# Slave.net
KiCad netlist of a schematic drawn in Altium Designer
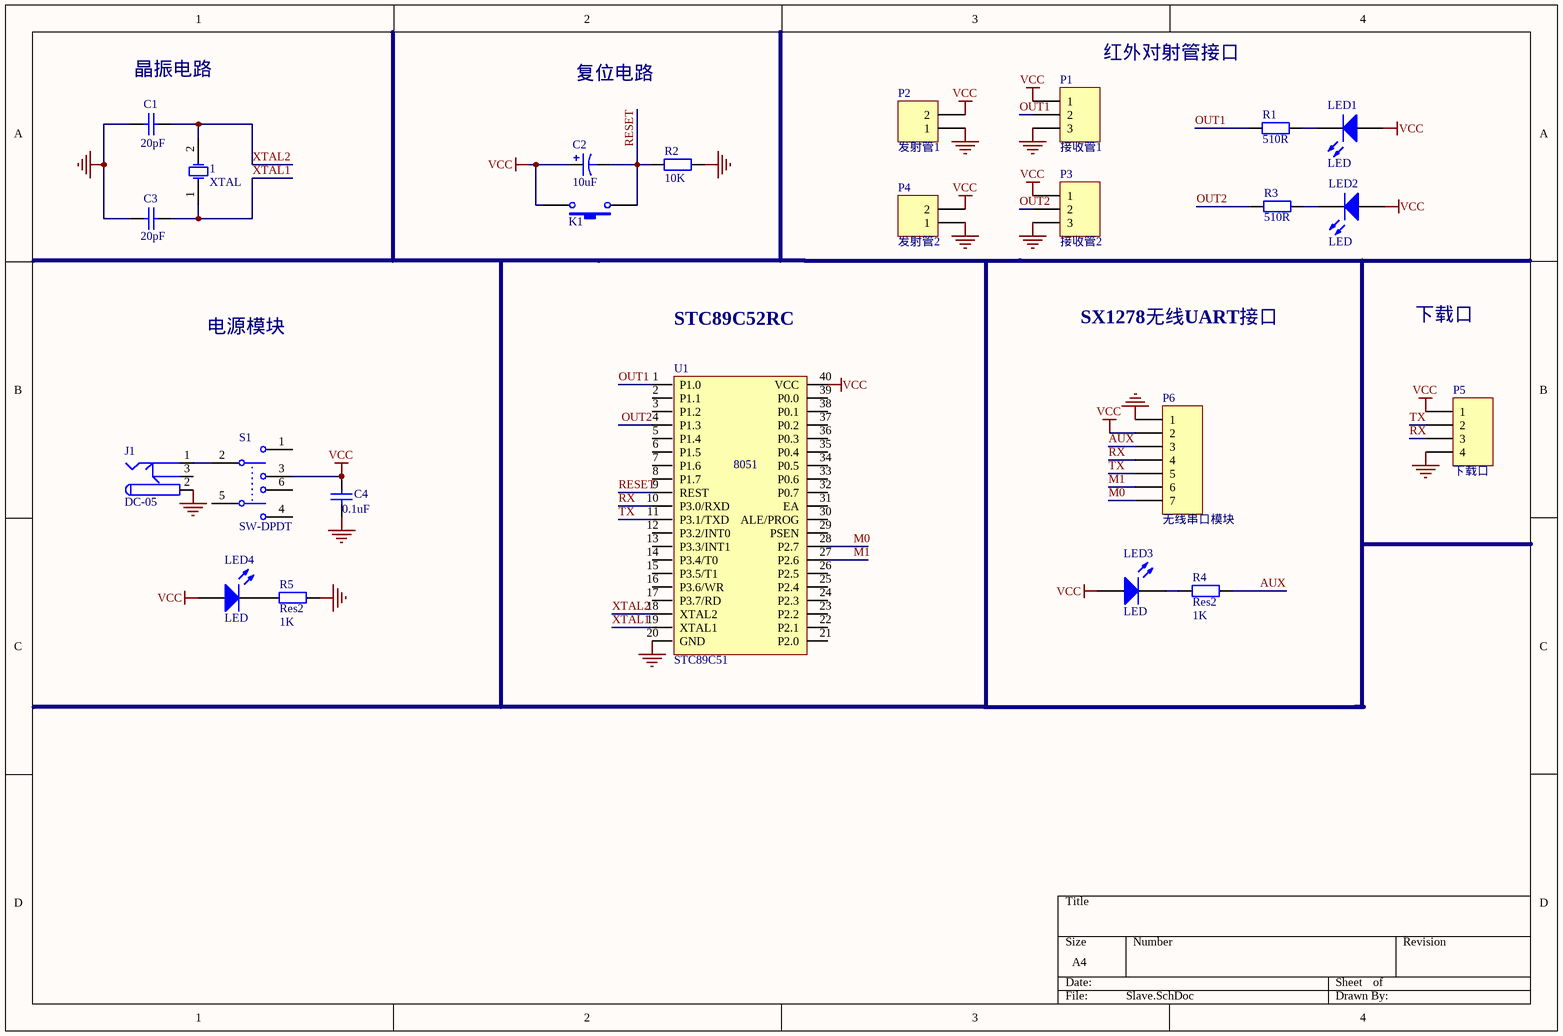
[diagram p0: Slave.SchDoc]

(export (version "E")
  (design (tool "Eeschema 10.0.6"))
  (components
    (comp (ref "1")
      (value "XTAL")
      (footprint "XTAL_US")
      (description "Crystal Oscillator")
      (fields (field (name "PUBLISHER") "Altium Limited"))
      (libsource (lib "Miscellaneous Devices") (part "XTAL"))
    )
    (comp (ref "C1")
      (value "20pF")
      (footprint "RAD-0.1")
      (description "Capacitor")
      (fields (field (name "Comment") "Cap") (field (name "PUBLISHER") "Altium Limited"))
      (libsource (lib "Miscellaneous Devices") (part "Cap"))
    )
    (comp (ref "C2")
      (value "10uF")
      (footprint "RB.1/.2")
      (description "Polarized Capacitor (Radial)")
      (fields (field (name "Comment") "Cap Pol1") (field (name "PUBLISHER") "Altium Limited"))
      (libsource (lib "Miscellaneous Devices") (part "Cap Pol1"))
    )
    (comp (ref "C3")
      (value "20pF")
      (footprint "RAD-0.1")
      (description "Capacitor")
      (fields (field (name "Comment") "Cap") (field (name "PUBLISHER") "Altium Limited"))
      (libsource (lib "Miscellaneous Devices") (part "Cap"))
    )
    (comp (ref "C4")
      (value "0.1uF")
      (footprint "RAD-0.1")
      (description "Capacitor")
      (fields (field (name "Comment") "Cap") (field (name "PUBLISHER") "Altium Limited"))
      (libsource (lib "Miscellaneous Devices") (part "Cap"))
    )
    (comp (ref "J1") (value "DC-05") (footprint "DC-05") (libsource (lib "My library") (part "DC-05")))
    (comp (ref "K1") (value "四脚按键") (footprint "四脚按键") (libsource (lib "My library") (part "四脚按键")))
    (comp (ref "LED1") (value "LED") (footprint "LED") (libsource (lib "My library") (part "LED")))
    (comp (ref "LED2") (value "LED") (footprint "LED") (libsource (lib "My library") (part "LED")))
    (comp (ref "LED3") (value "LED") (footprint "LED") (libsource (lib "My library") (part "LED")))
    (comp (ref "LED4") (value "LED") (footprint "LED") (libsource (lib "My library") (part "LED")))
    (comp (ref "P1")
      (value "接收管1")
      (footprint "HDR1X3")
      (description "Header, 3-Pin")
      (fields (field (name "PUBLISHER") "Altium Limited"))
      (libsource (lib "Miscellaneous Connectors") (part "Header 3"))
    )
    (comp (ref "P2")
      (value "发射管1")
      (footprint "HDR1X2")
      (description "Header, 2-Pin")
      (fields (field (name "PUBLISHER") "Altium Limited"))
      (libsource (lib "Miscellaneous Connectors") (part "Header 2"))
    )
    (comp (ref "P3")
      (value "接收管2")
      (footprint "HDR1X3")
      (description "Header, 3-Pin")
      (fields (field (name "PUBLISHER") "Altium Limited"))
      (libsource (lib "Miscellaneous Connectors") (part "Header 3"))
    )
    (comp (ref "P4")
      (value "发射管2")
      (footprint "HDR1X2")
      (description "Header, 2-Pin")
      (fields (field (name "PUBLISHER") "Altium Limited"))
      (libsource (lib "Miscellaneous Connectors") (part "Header 2"))
    )
    (comp (ref "P5")
      (value "下载口")
      (footprint "HDR1X4")
      (description "Header, 4-Pin")
      (fields (field (name "PUBLISHER") "Altium Limited"))
      (libsource (lib "Miscellaneous Connectors") (part "Header 4"))
    )
    (comp (ref "P6")
      (value "无线串口模块")
      (footprint "AS32-TTL-100")
      (description "Header, 7-Pin")
      (fields (field (name "PUBLISHER") "Altium Limited"))
      (libsource (lib "Miscellaneous Connectors") (part "Header 7"))
    )
    (comp (ref "R1")
      (value "510R")
      (footprint "AXIAL-0.4")
      (description "Resistor")
      (fields (field (name "Comment") "Res2") (field (name "PUBLISHER") "Altium Limited"))
      (libsource (lib "Miscellaneous Devices") (part "Res2"))
    )
    (comp (ref "R2")
      (value "10K")
      (footprint "AXIAL-0.4")
      (description "Resistor")
      (fields (field (name "Comment") "Res2") (field (name "PUBLISHER") "Altium Limited"))
      (libsource (lib "Miscellaneous Devices") (part "Res2"))
    )
    (comp (ref "R3")
      (value "510R")
      (footprint "AXIAL-0.4")
      (description "Resistor")
      (fields (field (name "Comment") "Res2") (field (name "PUBLISHER") "Altium Limited"))
      (libsource (lib "Miscellaneous Devices") (part "Res2"))
    )
    (comp (ref "R4")
      (value "Res2")
      (footprint "AXIAL-0.4")
      (description "Resistor")
      (fields (field (name "ALTIUM_VALUE") "1K") (field (name "PUBLISHER") "Altium Limited"))
      (libsource (lib "Miscellaneous Devices") (part "Res2"))
    )
    (comp (ref "R5")
      (value "Res2")
      (footprint "AXIAL-0.4")
      (description "Resistor")
      (fields (field (name "ALTIUM_VALUE") "1K") (field (name "PUBLISHER") "Altium Limited"))
      (libsource (lib "Miscellaneous Devices") (part "Res2"))
    )
    (comp (ref "S1")
      (value "SW-DPDT")
      (footprint "SWITCH_B1")
      (description "单刀双掷开关")
      (fields (field (name "PUBLISHER") "Altium Limited"))
      (libsource (lib "Fszhang") (part "SW-DPDT"))
    )
    (comp (ref "U1") (value "STC89C51") (footprint "DIP-40") (libsource (lib "My library") (part "STC89C51")))
  )
  (nets
    (net (code "1") (name "/AUX") (class "Default")
      (node (ref "P6") (pin "3") (pinfunction "3_3") (pintype "passive"))
      (node (ref "R4") (pin "2") (pinfunction "2_2") (pintype "passive"))
    )
    (net (code "2") (name "/M0") (class "Default")
      (node (ref "P6") (pin "7") (pinfunction "7_7") (pintype "passive"))
      (node (ref "U1") (pin "28") (pinfunction "P2.7_28") (pintype "passive"))
    )
    (net (code "3") (name "/M1") (class "Default")
      (node (ref "P6") (pin "6") (pinfunction "6_6") (pintype "passive"))
      (node (ref "U1") (pin "27") (pinfunction "P2.6_27") (pintype "passive"))
    )
    (net (code "4") (name "/OUT1") (class "Default")
      (node (ref "P1") (pin "2") (pinfunction "2_2") (pintype "passive"))
      (node (ref "R1") (pin "1") (pinfunction "1_1") (pintype "passive"))
      (node (ref "U1") (pin "1") (pinfunction "P1.0_1") (pintype "passive"))
    )
    (net (code "5") (name "/OUT2") (class "Default")
      (node (ref "P3") (pin "2") (pinfunction "2_2") (pintype "passive"))
      (node (ref "R3") (pin "1") (pinfunction "1_1") (pintype "passive"))
      (node (ref "U1") (pin "4") (pinfunction "P1.3_4") (pintype "passive"))
    )
    (net (code "6") (name "/RESET") (class "Default")
      (node (ref "C2") (pin "2") (pinfunction "2_2") (pintype "passive"))
      (node (ref "K1") (pin "1") (pinfunction "1_1") (pintype "passive"))
      (node (ref "R2") (pin "1") (pinfunction "1_1") (pintype "passive"))
      (node (ref "U1") (pin "9") (pinfunction "REST_9") (pintype "passive"))
    )
    (net (code "7") (name "/RX") (class "Default")
      (node (ref "P5") (pin "3") (pinfunction "3_3") (pintype "passive"))
      (node (ref "P6") (pin "4") (pinfunction "4_4") (pintype "passive"))
      (node (ref "U1") (pin "10") (pinfunction "P3.0/RXD_10") (pintype "passive"))
    )
    (net (code "8") (name "/TX") (class "Default")
      (node (ref "P5") (pin "2") (pinfunction "2_2") (pintype "passive"))
      (node (ref "P6") (pin "5") (pinfunction "5_5") (pintype "passive"))
      (node (ref "U1") (pin "11") (pinfunction "P3.1/TXD_11") (pintype "passive"))
    )
    (net (code "9") (name "/XTAL1") (class "Default")
      (node (ref "1") (pin "1") (pinfunction "OSC1_1") (pintype "passive"))
      (node (ref "C3") (pin "2") (pinfunction "2_2") (pintype "passive"))
      (node (ref "U1") (pin "19") (pinfunction "XTAL1_19") (pintype "passive"))
    )
    (net (code "10") (name "/XTAL2") (class "Default")
      (node (ref "1") (pin "2") (pinfunction "OSC2_2") (pintype "passive"))
      (node (ref "C1") (pin "2") (pinfunction "2_2") (pintype "passive"))
      (node (ref "U1") (pin "18") (pinfunction "XTAL2_18") (pintype "passive"))
    )
    (net (code "11") (name "GND") (class "Default")
      (node (ref "C1") (pin "1") (pinfunction "1_1") (pintype "passive"))
      (node (ref "C3") (pin "1") (pinfunction "1_1") (pintype "passive"))
      (node (ref "C4") (pin "1") (pinfunction "1_1") (pintype "passive"))
      (node (ref "J1") (pin "2") (pinfunction "2_2") (pintype "passive"))
      (node (ref "P1") (pin "3") (pinfunction "3_3") (pintype "passive"))
      (node (ref "P2") (pin "1") (pinfunction "1_1") (pintype "passive"))
      (node (ref "P3") (pin "3") (pinfunction "3_3") (pintype "passive"))
      (node (ref "P4") (pin "1") (pinfunction "1_1") (pintype "passive"))
      (node (ref "P5") (pin "4") (pinfunction "4_4") (pintype "passive"))
      (node (ref "P6") (pin "1") (pinfunction "1_1") (pintype "passive"))
      (node (ref "R2") (pin "2") (pinfunction "2_2") (pintype "passive"))
      (node (ref "R5") (pin "2") (pinfunction "2_2") (pintype "passive"))
      (node (ref "U1") (pin "20") (pinfunction "GND_20") (pintype "passive"))
    )
    (net (code "12") (name "Net-(J1-Pad1)") (class "Default")
      (node (ref "J1") (pin "1") (pinfunction "1_1") (pintype "passive"))
      (node (ref "S1") (pin "2") (pinfunction "2_2") (pintype "passive"))
    )
    (net (code "13") (name "Net-(LED1-Pad2)") (class "Default")
      (node (ref "LED1") (pin "2") (pinfunction "2_2") (pintype "passive"))
      (node (ref "R1") (pin "2") (pinfunction "2_2") (pintype "passive"))
    )
    (net (code "14") (name "Net-(LED2-Pad2)") (class "Default")
      (node (ref "LED2") (pin "2") (pinfunction "2_2") (pintype "passive"))
      (node (ref "R3") (pin "2") (pinfunction "2_2") (pintype "passive"))
    )
    (net (code "15") (name "Net-(LED3-Pad2)") (class "Default")
      (node (ref "LED3") (pin "2") (pinfunction "2_2") (pintype "passive"))
      (node (ref "R4") (pin "1") (pinfunction "1_1") (pintype "passive"))
    )
    (net (code "16") (name "Net-(LED4-Pad2)") (class "Default")
      (node (ref "LED4") (pin "2") (pinfunction "2_2") (pintype "passive"))
      (node (ref "R5") (pin "1") (pinfunction "1_1") (pintype "passive"))
    )
    (net (code "17") (name "VCC") (class "Default")
      (node (ref "C2") (pin "1") (pinfunction "1_1") (pintype "passive"))
      (node (ref "C4") (pin "2") (pinfunction "2_2") (pintype "passive"))
      (node (ref "K1") (pin "2") (pinfunction "2_2") (pintype "passive"))
      (node (ref "LED1") (pin "1") (pinfunction "1_1") (pintype "passive"))
      (node (ref "LED2") (pin "1") (pinfunction "1_1") (pintype "passive"))
      (node (ref "LED3") (pin "1") (pinfunction "1_1") (pintype "passive"))
      (node (ref "LED4") (pin "1") (pinfunction "1_1") (pintype "passive"))
      (node (ref "P1") (pin "1") (pinfunction "1_1") (pintype "passive"))
      (node (ref "P2") (pin "2") (pinfunction "2_2") (pintype "passive"))
      (node (ref "P3") (pin "1") (pinfunction "1_1") (pintype "passive"))
      (node (ref "P4") (pin "2") (pinfunction "2_2") (pintype "passive"))
      (node (ref "P5") (pin "1") (pinfunction "1_1") (pintype "passive"))
      (node (ref "P6") (pin "2") (pinfunction "2_2") (pintype "passive"))
      (node (ref "S1") (pin "3") (pinfunction "3_3") (pintype "passive"))
      (node (ref "U1") (pin "40") (pinfunction "VCC_40") (pintype "passive"))
    )
    (net (code "18") (name "unconnected-(J1-Pad3)") (class "Default")
      (node (ref "J1") (pin "3") (pinfunction "3_3") (pintype "passive"))
    )
    (net (code "19") (name "unconnected-(S1-Pad1)") (class "Default")
      (node (ref "S1") (pin "1") (pinfunction "1_1") (pintype "passive"))
    )
    (net (code "20") (name "unconnected-(S1-Pad4)") (class "Default")
      (node (ref "S1") (pin "4") (pinfunction "4_4") (pintype "passive"))
    )
    (net (code "21") (name "unconnected-(S1-Pad5)") (class "Default")
      (node (ref "S1") (pin "5") (pinfunction "5_5") (pintype "passive"))
    )
    (net (code "22") (name "unconnected-(S1-Pad6)") (class "Default")
      (node (ref "S1") (pin "6") (pinfunction "6_6") (pintype "passive"))
    )
    (net (code "23") (name "unconnected-(U1-ALE{slash}PROG-Pad30)") (class "Default")
      (node (ref "U1") (pin "30") (pinfunction "ALE/PROG_30") (pintype "passive"))
    )
    (net (code "24") (name "unconnected-(U1-EA-Pad31)") (class "Default")
      (node (ref "U1") (pin "31") (pinfunction "EA_31") (pintype "passive"))
    )
    (net (code "25") (name "unconnected-(U1-P0.0-Pad39)") (class "Default")
      (node (ref "U1") (pin "39") (pinfunction "P0.0_39") (pintype "passive"))
    )
    (net (code "26") (name "unconnected-(U1-P0.1-Pad38)") (class "Default")
      (node (ref "U1") (pin "38") (pinfunction "P0.1_38") (pintype "passive"))
    )
    (net (code "27") (name "unconnected-(U1-P0.2-Pad37)") (class "Default")
      (node (ref "U1") (pin "37") (pinfunction "P0.2_37") (pintype "passive"))
    )
    (net (code "28") (name "unconnected-(U1-P0.3-Pad36)") (class "Default")
      (node (ref "U1") (pin "36") (pinfunction "P0.3_36") (pintype "passive"))
    )
    (net (code "29") (name "unconnected-(U1-P0.4-Pad35)") (class "Default")
      (node (ref "U1") (pin "35") (pinfunction "P0.4_35") (pintype "passive"))
    )
    (net (code "30") (name "unconnected-(U1-P0.5-Pad34)") (class "Default")
      (node (ref "U1") (pin "34") (pinfunction "P0.5_34") (pintype "passive"))
    )
    (net (code "31") (name "unconnected-(U1-P0.6-Pad33)") (class "Default")
      (node (ref "U1") (pin "33") (pinfunction "P0.6_33") (pintype "passive"))
    )
    (net (code "32") (name "unconnected-(U1-P0.7-Pad32)") (class "Default")
      (node (ref "U1") (pin "32") (pinfunction "P0.7_32") (pintype "passive"))
    )
    (net (code "33") (name "unconnected-(U1-P1.1-Pad2)") (class "Default")
      (node (ref "U1") (pin "2") (pinfunction "P1.1_2") (pintype "passive"))
    )
    (net (code "34") (name "unconnected-(U1-P1.2-Pad3)") (class "Default")
      (node (ref "U1") (pin "3") (pinfunction "P1.2_3") (pintype "passive"))
    )
    (net (code "35") (name "unconnected-(U1-P1.4-Pad5)") (class "Default")
      (node (ref "U1") (pin "5") (pinfunction "P1.4_5") (pintype "passive"))
    )
    (net (code "36") (name "unconnected-(U1-P1.5-Pad6)") (class "Default")
      (node (ref "U1") (pin "6") (pinfunction "P1.5_6") (pintype "passive"))
    )
    (net (code "37") (name "unconnected-(U1-P1.6-Pad7)") (class "Default")
      (node (ref "U1") (pin "7") (pinfunction "P1.6_7") (pintype "passive"))
    )
    (net (code "38") (name "unconnected-(U1-P1.7-Pad8)") (class "Default")
      (node (ref "U1") (pin "8") (pinfunction "P1.7_8") (pintype "passive"))
    )
    (net (code "39") (name "unconnected-(U1-P2.0-Pad21)") (class "Default")
      (node (ref "U1") (pin "21") (pinfunction "P2.0_21") (pintype "passive"))
    )
    (net (code "40") (name "unconnected-(U1-P2.1-Pad22)") (class "Default")
      (node (ref "U1") (pin "22") (pinfunction "P2.1_22") (pintype "passive"))
    )
    (net (code "41") (name "unconnected-(U1-P2.2-Pad23)") (class "Default")
      (node (ref "U1") (pin "23") (pinfunction "P2.2_23") (pintype "passive"))
    )
    (net (code "42") (name "unconnected-(U1-P2.3-Pad24)") (class "Default")
      (node (ref "U1") (pin "24") (pinfunction "P2.3_24") (pintype "passive"))
    )
    (net (code "43") (name "unconnected-(U1-P2.4-Pad25)") (class "Default")
      (node (ref "U1") (pin "25") (pinfunction "P2.4_25") (pintype "passive"))
    )
    (net (code "44") (name "unconnected-(U1-P2.5-Pad26)") (class "Default")
      (node (ref "U1") (pin "26") (pinfunction "P2.5_26") (pintype "passive"))
    )
    (net (code "45") (name "unconnected-(U1-P3.2{slash}INT0-Pad12)") (class "Default")
      (node (ref "U1") (pin "12") (pinfunction "P3.2/INT0_12") (pintype "passive"))
    )
    (net (code "46") (name "unconnected-(U1-P3.3{slash}INT1-Pad13)") (class "Default")
      (node (ref "U1") (pin "13") (pinfunction "P3.3/INT1_13") (pintype "passive"))
    )
    (net (code "47") (name "unconnected-(U1-P3.4{slash}T0-Pad14)") (class "Default")
      (node (ref "U1") (pin "14") (pinfunction "P3.4/T0_14") (pintype "passive"))
    )
    (net (code "48") (name "unconnected-(U1-P3.5{slash}T1-Pad15)") (class "Default")
      (node (ref "U1") (pin "15") (pinfunction "P3.5/T1_15") (pintype "passive"))
    )
    (net (code "49") (name "unconnected-(U1-P3.6{slash}WR-Pad16)") (class "Default")
      (node (ref "U1") (pin "16") (pinfunction "P3.6/WR_16") (pintype "passive"))
    )
    (net (code "50") (name "unconnected-(U1-P3.7{slash}RD-Pad17)") (class "Default")
      (node (ref "U1") (pin "17") (pinfunction "P3.7/RD_17") (pintype "passive"))
    )
    (net (code "51") (name "unconnected-(U1-PSEN-Pad29)") (class "Default")
      (node (ref "U1") (pin "29") (pinfunction "PSEN_29") (pintype "passive"))
    )
  )
)
